# Motor_12V_Buck.net
KiCad netlist of a schematic drawn in Altium Designer
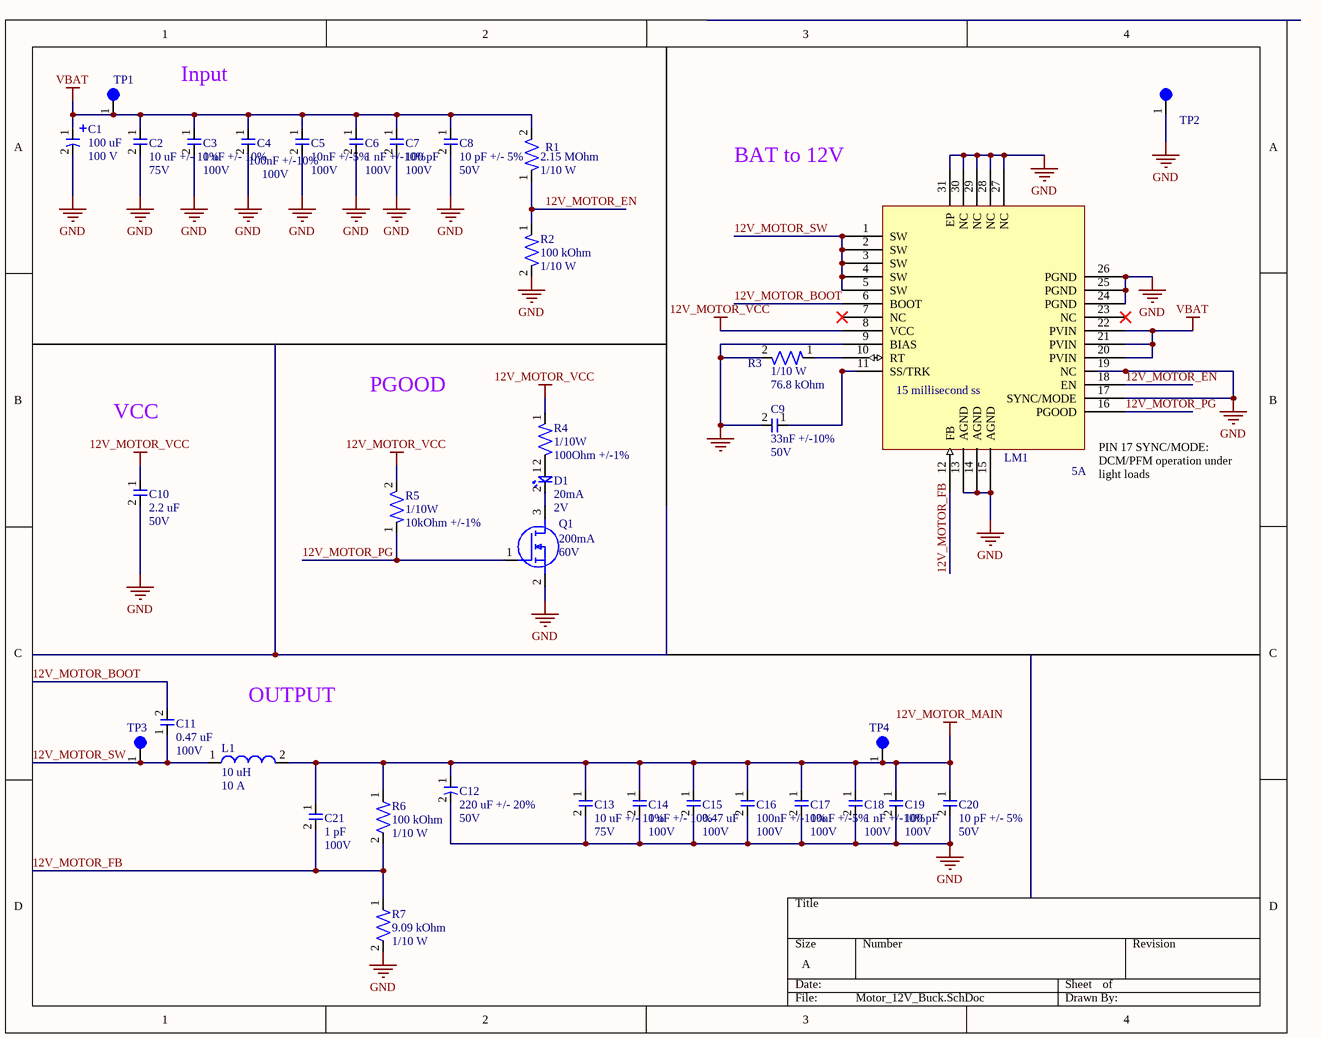
[diagram p0: Motor_12V_Buck.SchDoc]

(export (version "E")
  (design (tool "Eeschema 10.0.6"))
  (components
    (comp (ref "C1")
      (value "100SEV100M12.5X16")
      (footprint "ELEC-100U-0001")
      (description "100 µF 100 V Aluminum Electrolytic Capacitors Radial, Can - SMD 2000 Hrs @ 85°C")
      (fields
        (field (name "MANUFACTURER") "Rubycon")
        (field (name "TOLERANCE") "+/- 20%")
        (field (name "CAPACITANCE") "100 uF")
        (field (name "VOLTAGE") "100 V")
      )
      (libsource (lib "MasterLib") (part "ELEC-100U-0001"))
    )
    (comp (ref "C2")
      (value "C3225X7R1N106K250AC")
      (footprint "CAP-1210")
      (description "10 µF ±10% 75V Ceramic Capacitor X7R 1210 (3225 Metric)")
      (fields (field (name "CAPACITANCE") "10 uF +/- 10%") (field (name "VOLTAGE RATING") "75V"))
      (libsource (lib "MasterLib") (part "CAP-10U-0004"))
    )
    (comp (ref "C3")
      (value "CL31B105KCHNNNE")
      (footprint "CAP-1206 - duplicate")
      (description "1 µF ±10% 100V Ceramic Capacitor X7R 1206 (3216 Metric)")
      (fields (field (name "CAPACITANCE") "1 uF +/- 10%") (field (name "VOLTAGE") "100V"))
      (libsource (lib "MasterLib") (part "CAP-1U-0001"))
    )
    (comp (ref "C4")
      (value "CC0603KRX7R0BB104")
      (footprint "CAP-0603")
      (description "CAP CER 0.1UF 100V X7R 0603")
      (fields
        (field (name "MANUFACTURER") "YAGEO")
        (field (name "CAPACITANCE") "100nF +/-10%")
        (field (name "VOLTAGE RATING") "100V")
      )
      (libsource (lib "MasterLib") (part "CAP-100N-0001"))
    )
    (comp (ref "C5")
      (value "C1608C0G2A103J080AC")
      (footprint "CAP-0603")
      (description "CAP CER 10000PF 100V C0G 0603")
      (fields
        (field (name "MANUFACTURER") "TDK Corporation")
        (field (name "CAPACITANCE") "10nF +/-5%")
        (field (name "VOLTAGE RATING") "100V")
      )
      (libsource (lib "MasterLib") (part "CAP-10N-0002"))
    )
    (comp (ref "C6")
      (value "C0603Y102K1RAC7867")
      (footprint "CAP-0603")
      (description "1000 pF ±10% 100V Ceramic Capacitor X7R 0603 (1608 Metric)")
      (fields (field (name "CAPACITANCE") "1 nF +/-10%") (field (name "VOLTAGE") "100V"))
      (libsource (lib "MasterLib") (part "CAP-1N-0001"))
    )
    (comp (ref "C7")
      (value "0603N101J101CT")
      (footprint "CAP-0603")
      (description "100 pF ±5% 100V Ceramic Capacitor C0G, NP0 0603 (1608 Metric)")
      (fields
        (field (name "TOLERANCE") "+/-5%")
        (field (name "CAPACITANCE") "100 pF")
        (field (name "VOLTAGE") "100V")
      )
      (libsource (lib "MasterLib") (part "CAP-100P-0002"))
    )
    (comp (ref "C8")
      (value "0603N100J500CT")
      (footprint "CAP-0603")
      (description "10 pF ±5% 50V Ceramic Capacitor C0G, NP0 0603 (1608 Metric)")
      (fields
        (field (name "MANUFACTURER") "Walshin Technology Corporation")
        (field (name "CAPACITANCE") "10 pF +/- 5%")
        (field (name "VOLTAGE RATING") "50V")
      )
      (libsource (lib "MasterLib") (part "CAP-10P-0001"))
    )
    (comp (ref "C9")
      (value "CC0603KRX7R9BB333")
      (footprint "CAP-0603")
      (description "0.033 µF ±10% 50V Ceramic Capacitor X7R 0603 (1608 Metric)")
      (fields
        (field (name "MANUFACTURER") "YAGEO")
        (field (name "CAPACITANCE") "33nF +/-10%")
        (field (name "VOLTAGE RATING") "50V")
      )
      (libsource (lib "MasterLib") (part "CAP-33N-0001"))
    )
    (comp (ref "C10")
      (value "UMK107BBJ225KA-T")
      (footprint "CAP-0603")
      (description "2.2 µF ±10% 50V Ceramic Capacitor X5R 0603 (1608 Metric)")
      (fields (field (name "CAPACITANCE") "2.2 uF") (field (name "OLTAGE") "50V"))
      (libsource (lib "MasterLib") (part "CAP-2.2U-0001"))
    )
    (comp (ref "C11")
      (value "KAM21KR72A474KL")
      (footprint "CAP-0805")
      (description "0.47 µF ±10% 100V Ceramic Capacitor X7R 0805 (2012 Metric)")
      (fields
        (field (name "TOLERANCE") "+/- 10%")
        (field (name "CAPACITANCE") "0.47 uF")
        (field (name "VOLTAGE") "100V")
      )
      (libsource (lib "MasterLib") (part "CAP-0.47U-0001"))
    )
    (comp (ref "C12")
      (value "50TZV220M10X10.5")
      (footprint "ELEC-220U-0003")
      (description "220 µF 50 V Aluminum Electrolytic Capacitors Radial, Can - SMD 2000 Hrs @ 105°C")
      (fields (field (name "CAPACITANCE") "220 uF +/- 20%") (field (name "VOLTAGE RATING") "50V"))
      (libsource (lib "MasterLib") (part "ELEC-220U-0003"))
    )
    (comp (ref "C13")
      (value "C3225X7R1N106K250AC")
      (footprint "CAP-1210")
      (description "10 µF ±10% 75V Ceramic Capacitor X7R 1210 (3225 Metric)")
      (fields (field (name "CAPACITANCE") "10 uF +/- 10%") (field (name "VOLTAGE RATING") "75V"))
      (libsource (lib "MasterLib") (part "CAP-10U-0004"))
    )
    (comp (ref "C14")
      (value "CL31B105KCHNNNE")
      (footprint "CAP-1206 - duplicate")
      (description "1 µF ±10% 100V Ceramic Capacitor X7R 1206 (3216 Metric)")
      (fields (field (name "CAPACITANCE") "1 uF +/- 10%") (field (name "VOLTAGE") "100V"))
      (libsource (lib "MasterLib") (part "CAP-1U-0001"))
    )
    (comp (ref "C15")
      (value "KAM21KR72A474KL")
      (footprint "CAP-0805")
      (description "0.47 µF ±10% 100V Ceramic Capacitor X7R 0805 (2012 Metric)")
      (fields
        (field (name "TOLERANCE") "+/- 10%")
        (field (name "CAPACITANCE") "0.47 uF")
        (field (name "VOLTAGE") "100V")
      )
      (libsource (lib "MasterLib") (part "CAP-0.47U-0001"))
    )
    (comp (ref "C16")
      (value "CC0603KRX7R0BB104")
      (footprint "CAP-0603")
      (description "CAP CER 0.1UF 100V X7R 0603")
      (fields
        (field (name "MANUFACTURER") "YAGEO")
        (field (name "CAPACITANCE") "100nF +/-10%")
        (field (name "VOLTAGE RATING") "100V")
      )
      (libsource (lib "MasterLib") (part "CAP-100N-0001"))
    )
    (comp (ref "C17")
      (value "C1608C0G2A103J080AC")
      (footprint "CAP-0603")
      (description "CAP CER 10000PF 100V C0G 0603")
      (fields
        (field (name "MANUFACTURER") "TDK Corporation")
        (field (name "CAPACITANCE") "10nF +/-5%")
        (field (name "VOLTAGE RATING") "100V")
      )
      (libsource (lib "MasterLib") (part "CAP-10N-0002"))
    )
    (comp (ref "C18")
      (value "C0603Y102K1RAC7867")
      (footprint "CAP-0603")
      (description "1000 pF ±10% 100V Ceramic Capacitor X7R 0603 (1608 Metric)")
      (fields (field (name "CAPACITANCE") "1 nF +/-10%") (field (name "VOLTAGE") "100V"))
      (libsource (lib "MasterLib") (part "CAP-1N-0001"))
    )
    (comp (ref "C19")
      (value "0603N101J101CT")
      (footprint "CAP-0603")
      (description "100 pF ±5% 100V Ceramic Capacitor C0G, NP0 0603 (1608 Metric)")
      (fields
        (field (name "TOLERANCE") "+/-5%")
        (field (name "CAPACITANCE") "100 pF")
        (field (name "VOLTAGE") "100V")
      )
      (libsource (lib "MasterLib") (part "CAP-100P-0002"))
    )
    (comp (ref "C20")
      (value "0603N100J500CT")
      (footprint "CAP-0603")
      (description "10 pF ±5% 50V Ceramic Capacitor C0G, NP0 0603 (1608 Metric)")
      (fields
        (field (name "MANUFACTURER") "Walshin Technology Corporation")
        (field (name "CAPACITANCE") "10 pF +/- 5%")
        (field (name "VOLTAGE RATING") "50V")
      )
      (libsource (lib "MasterLib") (part "CAP-10P-0001"))
    )
    (comp (ref "C21")
      (value "885012006087")
      (footprint "CAP-0603")
      (description "1 pF ±0.25pF 100V Ceramic Capacitor C0G, NP0 0603 (1608 Metric)")
      (fields
        (field (name "TOLERANCE") "+/- 0.25 pF")
        (field (name "CAPACITANCE") "1 pF")
        (field (name "VOLTAGE") "100V")
      )
      (libsource (lib "MasterLib") (part "CAP-1P-0001"))
    )
    (comp (ref "D1")
      (value "150060AS75000")
      (footprint "LED-0603")
      (description "CAP CER 0.1UF 100V X7R 0603")
      (fields
        (field (name "MANUFACTURER") "Wurth Electronik")
        (field (name "CURRENT RATING") "20mA")
        (field (name "VF") "2V")
      )
      (libsource (lib "MasterLib") (part "LED_Amber_0001"))
    )
    (comp (ref "L1")
      (value "SRP1270-100M")
      (footprint "PWRIND-10U-0002")
      (description "10 µH Shielded Drum Core, Wirewound Inductor 10 A 16.8mOhm Max Nonstandard")
      (fields
        (field (name "TOLERANCE") "+/- 20%")
        (field (name "INDUCTANCE") "10 uH")
        (field (name "DCI") "10 A")
      )
      (libsource (lib "MasterLib") (part "PWRIND-10U-0002"))
    )
    (comp (ref "LM1")
      (value "LM76005RNPR")
      (footprint "IC-30-WQFN(6x4)")
      (description "Buck Switching Regulator IC Positive Adjustable 1V 1 Output 5A 30-WFQFN Exposed Pad")
      (fields (field (name "MANUFACTURER") "Texas Instruments") (field (name "CURRENT") "5A"))
      (libsource (lib "MasterLib") (part "IC-BUCK-0006"))
    )
    (comp (ref "Q1")
      (value "T2N7002AK,LM")
      (footprint "NMOS-SOT23-3")
      (description "MOSFET N-CH 60V 200MA SOT23")
      (fields
        (field (name "MANUFACTURER") "Toshiba")
        (field (name "ID-CONTINUOUS") "200mA")
        (field (name "VDS-MAX") "60V")
      )
      (libsource (lib "MasterLib") (part "NMOS-200MA-0001"))
    )
    (comp (ref "R1")
      (value "RC0603FR-072M15L")
      (footprint "RES-0603")
      (description "2.15 MOhms ±1% 0.1W, 1/10W Chip Resistor 0603 (1608 Metric) Moisture Resistant Thick Film")
      (fields
        (field (name "TOLERANCE") "+/-1%")
        (field (name "RESISTANCE") "2.15 MOhm")
        (field (name "POWER") "1/10 W")
      )
      (libsource (lib "MasterLib") (part "RES-2.15M-0001"))
    )
    (comp (ref "R2")
      (value "RC0603FR-07100KL")
      (footprint "RES-0603")
      (description "100 kOhms ±1% 0.1W, 1/10W Chip Resistor 0603 (1608 Metric) Moisture Resistant Thick Film")
      (fields
        (field (name "TOLERANCE") "+/- 1%")
        (field (name "RESISTANCE") "100 kOhm")
        (field (name "POWER") "1/10 W")
      )
      (libsource (lib "MasterLib") (part "RES-100K-0003"))
    )
    (comp (ref "R3")
      (value "RC0603FR-0776K8L")
      (footprint "RES-0603")
      (description "76.8 kOhms ±1% 0.1W, 1/10W Chip Resistor 0603 (1608 Metric) Moisture Resistant Thick Film")
      (fields
        (field (name "MANUFACTURER") "Yageo")
        (field (name "TOLERANCE") "+/- 1%")
        (field (name "POWER") "1/10 W")
        (field (name "RESISTANCE") "76.8 kOhm")
      )
      (libsource (lib "MasterLib") (part "RES-76.8K-0001"))
    )
    (comp (ref "R4")
      (value "AC0603FR-10100RL")
      (footprint "RES-0603")
      (description "100 Ohms ±1% 0.1W, 1/10W Chip Resistor 0603 (1608 Metric) Automotive AEC-Q200 Thick Film")
      (fields
        (field (name "MANUFACTURER") "YAGEO")
        (field (name "POWER RATING") "1/10W")
        (field (name "RESISTANCE") "100Ohm +/-1%")
      )
      (libsource (lib "MasterLib") (part "RES-100-0002"))
    )
    (comp (ref "R5")
      (value "RC0603FR-0710KP")
      (footprint "RES-0603")
      (description "RES SMD 10K OHM 1% 1/10W 0603")
      (fields
        (field (name "MANUFACTURER") "YAGEO")
        (field (name "POWER RATING") "1/10W")
        (field (name "RESISTANCE") "10kOhm +/-1%")
      )
      (libsource (lib "MasterLib") (part "RES-10K-0002"))
    )
    (comp (ref "R6")
      (value "RC0603FR-07100KL")
      (footprint "RES-0603")
      (description "100 kOhms ±1% 0.1W, 1/10W Chip Resistor 0603 (1608 Metric) Moisture Resistant Thick Film")
      (fields
        (field (name "TOLERANCE") "+/- 1%")
        (field (name "RESISTANCE") "100 kOhm")
        (field (name "POWER") "1/10 W")
      )
      (libsource (lib "MasterLib") (part "RES-100K-0003"))
    )
    (comp (ref "R7")
      (value "RC0603FR-079K09L")
      (footprint "RES-0603")
      (description "9.09 kOhms ±1% 0.1W, 1/10W Chip Resistor 0603 (1608 Metric) Moisture Resistant Thick Film")
      (fields
        (field (name "TOLERANCE") "+/-1%")
        (field (name "RESISTANCE") "9.09 kOhm")
        (field (name "POWER") "1/10 W")
      )
      (libsource (lib "MasterLib") (part "RES-9.09K-0001"))
    )
    (comp (ref "TP1")
      (value "5003")
      (footprint "TEST-POINT-0001")
      (description "Oranange PC Test Point, Miniature Phoisphor Bronze Silver Plating Through Hole Mounting Type")
      (libsource (lib "MasterLib") (part "TEST-POINT-0001"))
    )
    (comp (ref "TP2")
      (value "5003")
      (footprint "TEST-POINT-0001")
      (description "Oranange PC Test Point, Miniature Phoisphor Bronze Silver Plating Through Hole Mounting Type")
      (libsource (lib "MasterLib") (part "TEST-POINT-0001"))
    )
    (comp (ref "TP3")
      (value "5003")
      (footprint "TEST-POINT-0001")
      (description "Oranange PC Test Point, Miniature Phoisphor Bronze Silver Plating Through Hole Mounting Type")
      (libsource (lib "MasterLib") (part "TEST-POINT-0001"))
    )
    (comp (ref "TP4")
      (value "5003")
      (footprint "TEST-POINT-0001")
      (description "Oranange PC Test Point, Miniature Phoisphor Bronze Silver Plating Through Hole Mounting Type")
      (libsource (lib "MasterLib") (part "TEST-POINT-0001"))
    )
  )
  (nets
    (net (code "1") (name "/12V_MOTOR_BOOT") (class "Default")
      (node (ref "C11") (pin "2") (pinfunction "2_2") (pintype "passive"))
      (node (ref "LM1") (pin "6") (pinfunction "BOOT_6") (pintype "power_in"))
    )
    (net (code "2") (name "/12V_MOTOR_EN") (class "Default")
      (node (ref "LM1") (pin "18") (pinfunction "EN_18") (pintype "power_in"))
      (node (ref "R1") (pin "1") (pinfunction "1_1") (pintype "passive"))
      (node (ref "R2") (pin "1") (pinfunction "1_1") (pintype "passive"))
    )
    (net (code "3") (name "/12V_MOTOR_FB") (class "Default")
      (node (ref "C21") (pin "2") (pinfunction "2_2") (pintype "passive"))
      (node (ref "LM1") (pin "12") (pinfunction "FB_12") (pintype "input"))
      (node (ref "R6") (pin "2") (pinfunction "2_2") (pintype "passive"))
      (node (ref "R7") (pin "1") (pinfunction "1_1") (pintype "passive"))
    )
    (net (code "4") (name "/12V_MOTOR_PG") (class "Default")
      (node (ref "LM1") (pin "16") (pinfunction "PGOOD_16") (pintype "power_in"))
      (node (ref "Q1") (pin "1") (pinfunction "G_1") (pintype "passive"))
      (node (ref "R5") (pin "1") (pinfunction "1_1") (pintype "passive"))
    )
    (net (code "5") (name "/12V_MOTOR_SW") (class "Default")
      (node (ref "C11") (pin "1") (pinfunction "1_1") (pintype "passive"))
      (node (ref "L1") (pin "1") (pinfunction "1_1") (pintype "passive"))
      (node (ref "LM1") (pin "1") (pinfunction "SW_1") (pintype "power_in"))
      (node (ref "LM1") (pin "2") (pinfunction "SW_2") (pintype "power_in"))
      (node (ref "LM1") (pin "3") (pinfunction "SW_3") (pintype "power_in"))
      (node (ref "LM1") (pin "4") (pinfunction "SW_4") (pintype "power_in"))
      (node (ref "LM1") (pin "5") (pinfunction "SW_5") (pintype "power_in"))
      (node (ref "TP3") (pin "1") (pinfunction "0_1") (pintype "passive"))
    )
    (net (code "6") (name "12V_MOTOR_MAIN") (class "Default")
      (node (ref "C12") (pin "1") (pinfunction "1_1") (pintype "passive"))
      (node (ref "C13") (pin "1") (pinfunction "1_1") (pintype "passive"))
      (node (ref "C14") (pin "1") (pinfunction "1_1") (pintype "passive"))
      (node (ref "C15") (pin "1") (pinfunction "1_1") (pintype "passive"))
      (node (ref "C16") (pin "1") (pinfunction "1_1") (pintype "passive"))
      (node (ref "C17") (pin "1") (pinfunction "1_1") (pintype "passive"))
      (node (ref "C18") (pin "1") (pinfunction "1_1") (pintype "passive"))
      (node (ref "C19") (pin "1") (pinfunction "1_1") (pintype "passive"))
      (node (ref "C20") (pin "1") (pinfunction "1_1") (pintype "passive"))
      (node (ref "C21") (pin "1") (pinfunction "1_1") (pintype "passive"))
      (node (ref "L1") (pin "2") (pinfunction "2_2") (pintype "passive"))
      (node (ref "R6") (pin "1") (pinfunction "1_1") (pintype "passive"))
      (node (ref "TP4") (pin "1") (pinfunction "0_1") (pintype "passive"))
    )
    (net (code "7") (name "12V_MOTOR_VCC") (class "Default")
      (node (ref "C10") (pin "1") (pinfunction "1_1") (pintype "passive"))
      (node (ref "LM1") (pin "8") (pinfunction "VCC_8") (pintype "power_in"))
      (node (ref "R4") (pin "1") (pinfunction "1_1") (pintype "passive"))
      (node (ref "R5") (pin "2") (pinfunction "2_2") (pintype "passive"))
    )
    (net (code "8") (name "<NO NET>") (class "Default")
      (node (ref "C9") (pin "2") (pinfunction "2_2") (pintype "passive"))
      (node (ref "LM1") (pin "9") (pinfunction "BIAS_9") (pintype "power_in"))
      (node (ref "R3") (pin "2") (pinfunction "2_2") (pintype "passive"))
    )
    (net (code "9") (name "GND") (class "Default")
      (node (ref "C1") (pin "2") (pinfunction "2_2") (pintype "passive"))
      (node (ref "C10") (pin "2") (pinfunction "2_2") (pintype "passive"))
      (node (ref "C12") (pin "2") (pinfunction "2_2") (pintype "passive"))
      (node (ref "C13") (pin "2") (pinfunction "2_2") (pintype "passive"))
      (node (ref "C14") (pin "2") (pinfunction "2_2") (pintype "passive"))
      (node (ref "C15") (pin "2") (pinfunction "2_2") (pintype "passive"))
      (node (ref "C16") (pin "2") (pinfunction "2_2") (pintype "passive"))
      (node (ref "C17") (pin "2") (pinfunction "2_2") (pintype "passive"))
      (node (ref "C18") (pin "2") (pinfunction "2_2") (pintype "passive"))
      (node (ref "C19") (pin "2") (pinfunction "2_2") (pintype "passive"))
      (node (ref "C2") (pin "2") (pinfunction "2_2") (pintype "passive"))
      (node (ref "C20") (pin "2") (pinfunction "2_2") (pintype "passive"))
      (node (ref "C3") (pin "2") (pinfunction "2_2") (pintype "passive"))
      (node (ref "C4") (pin "2") (pinfunction "2_2") (pintype "passive"))
      (node (ref "C5") (pin "2") (pinfunction "2_2") (pintype "passive"))
      (node (ref "C6") (pin "2") (pinfunction "2_2") (pintype "passive"))
      (node (ref "C7") (pin "2") (pinfunction "2_2") (pintype "passive"))
      (node (ref "C8") (pin "2") (pinfunction "2_2") (pintype "passive"))
      (node (ref "LM1") (pin "13") (pinfunction "AGND_13") (pintype "power_in"))
      (node (ref "LM1") (pin "14") (pinfunction "AGND_14") (pintype "power_in"))
      (node (ref "LM1") (pin "15") (pinfunction "AGND_15") (pintype "power_in"))
      (node (ref "LM1") (pin "17") (pinfunction "SYNC/MODE_17") (pintype "power_in"))
      (node (ref "LM1") (pin "19") (pinfunction "NC_19") (pintype "power_in"))
      (node (ref "LM1") (pin "24") (pinfunction "PGND_24") (pintype "power_in"))
      (node (ref "LM1") (pin "25") (pinfunction "PGND_25") (pintype "power_in"))
      (node (ref "LM1") (pin "26") (pinfunction "PGND_26") (pintype "power_in"))
      (node (ref "LM1") (pin "27") (pinfunction "NC_27") (pintype "power_in"))
      (node (ref "LM1") (pin "28") (pinfunction "NC_28") (pintype "power_in"))
      (node (ref "LM1") (pin "29") (pinfunction "NC_29") (pintype "power_in"))
      (node (ref "LM1") (pin "30") (pinfunction "NC_30") (pintype "power_in"))
      (node (ref "LM1") (pin "31") (pinfunction "EP_31") (pintype "power_in"))
      (node (ref "Q1") (pin "2") (pinfunction "S_2") (pintype "passive"))
      (node (ref "R2") (pin "2") (pinfunction "2_2") (pintype "passive"))
      (node (ref "R7") (pin "2") (pinfunction "2_2") (pintype "passive"))
      (node (ref "TP2") (pin "1") (pinfunction "0_1") (pintype "passive"))
    )
    (net (code "10") (name "Net-(D1-Pad1)") (class "Default")
      (node (ref "D1") (pin "1") (pinfunction "1_1") (pintype "passive"))
      (node (ref "R4") (pin "2") (pinfunction "2_2") (pintype "passive"))
    )
    (net (code "11") (name "Net-(LM1-RT)") (class "Default")
      (node (ref "LM1") (pin "10") (pinfunction "RT_10") (pintype "bidirectional"))
      (node (ref "R3") (pin "1") (pinfunction "1_1") (pintype "passive"))
    )
    (net (code "12") (name "Net-(LM1-SS{slash}TRK)") (class "Default")
      (node (ref "C9") (pin "1") (pinfunction "1_1") (pintype "passive"))
      (node (ref "LM1") (pin "11") (pinfunction "SS/TRK_11") (pintype "passive"))
    )
    (net (code "13") (name "Net-(Q1-D)") (class "Default")
      (node (ref "D1") (pin "2") (pinfunction "2_2") (pintype "passive"))
      (node (ref "Q1") (pin "3") (pinfunction "D_3") (pintype "passive"))
    )
    (net (code "14") (name "VBAT") (class "Default")
      (node (ref "C1") (pin "1") (pinfunction "1_1") (pintype "passive"))
      (node (ref "C2") (pin "1") (pinfunction "1_1") (pintype "passive"))
      (node (ref "C3") (pin "1") (pinfunction "1_1") (pintype "passive"))
      (node (ref "C4") (pin "1") (pinfunction "1_1") (pintype "passive"))
      (node (ref "C5") (pin "1") (pinfunction "1_1") (pintype "passive"))
      (node (ref "C6") (pin "1") (pinfunction "1_1") (pintype "passive"))
      (node (ref "C7") (pin "1") (pinfunction "1_1") (pintype "passive"))
      (node (ref "C8") (pin "1") (pinfunction "1_1") (pintype "passive"))
      (node (ref "LM1") (pin "20") (pinfunction "PVIN_20") (pintype "power_in"))
      (node (ref "LM1") (pin "21") (pinfunction "PVIN_21") (pintype "power_in"))
      (node (ref "LM1") (pin "22") (pinfunction "PVIN_22") (pintype "power_in"))
      (node (ref "R1") (pin "2") (pinfunction "2_2") (pintype "passive"))
      (node (ref "TP1") (pin "1") (pinfunction "0_1") (pintype "passive"))
    )
    (net (code "15") (name "unconnected-(LM1-NC-Pad7)") (class "Default")
      (node (ref "LM1") (pin "7") (pinfunction "NC_7") (pintype "power_in+no_connect"))
    )
    (net (code "16") (name "unconnected-(LM1-NC-Pad23)") (class "Default")
      (node (ref "LM1") (pin "23") (pinfunction "NC_23") (pintype "tri_state+no_connect"))
    )
  )
)
